# Projekt_Sch.net
KiCad netlist of a schematic drawn in Altium Designer
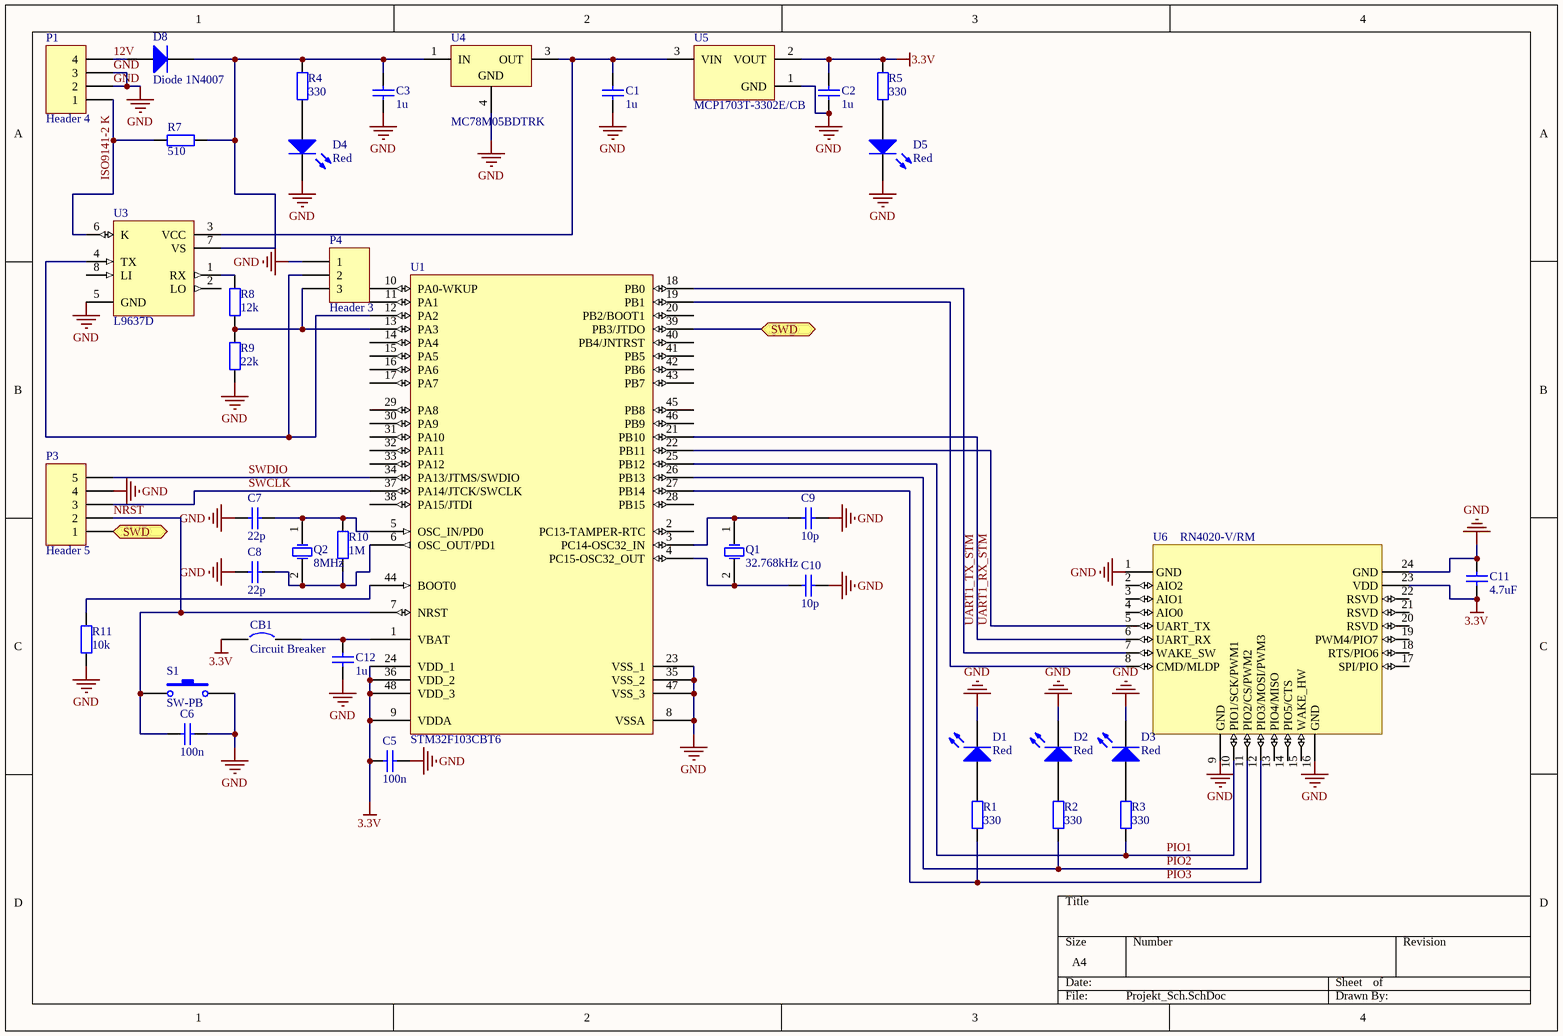
[diagram p0: Projekt_Sch.SchDoc]

(export (version "E")
  (design (tool "Eeschema 10.0.6"))
  (components
    (comp (ref "C1")
      (value "1u")
      (footprint "0402")
      (description "Capacitor")
      (fields (field (name "PUBLISHER") "Altium Limited"))
      (libsource (lib "Miscellaneous Devices") (part "Cap"))
    )
    (comp (ref "C2")
      (value "1u")
      (footprint "0402")
      (description "Capacitor")
      (fields (field (name "PUBLISHER") "Altium Limited"))
      (libsource (lib "Miscellaneous Devices") (part "Cap"))
    )
    (comp (ref "C3")
      (value "1u")
      (footprint "0603")
      (description "Capacitor")
      (fields (field (name "PUBLISHER") "Altium Limited"))
      (libsource (lib "Miscellaneous Devices") (part "Cap"))
    )
    (comp (ref "C5")
      (value "100n")
      (footprint "0402")
      (description "Capacitor")
      (fields (field (name "PUBLISHER") "Altium Limited"))
      (libsource (lib "Miscellaneous Devices") (part "Cap"))
    )
    (comp (ref "C6")
      (value "100n")
      (footprint "0402")
      (description "Capacitor")
      (fields (field (name "PUBLISHER") "Altium Limited"))
      (libsource (lib "Miscellaneous Devices") (part "Cap"))
    )
    (comp (ref "C7")
      (value "22p")
      (footprint "0402")
      (description "Capacitor")
      (fields (field (name "PUBLISHER") "Altium Limited"))
      (libsource (lib "Miscellaneous Devices") (part "Cap"))
    )
    (comp (ref "C8")
      (value "22p")
      (footprint "0402")
      (description "Capacitor")
      (fields (field (name "PUBLISHER") "Altium Limited"))
      (libsource (lib "Miscellaneous Devices") (part "Cap"))
    )
    (comp (ref "C9")
      (value "10p")
      (footprint "0402")
      (description "Capacitor")
      (fields (field (name "PUBLISHER") "Altium Limited"))
      (libsource (lib "Miscellaneous Devices") (part "Cap"))
    )
    (comp (ref "C10")
      (value "10p")
      (footprint "0402")
      (description "Capacitor")
      (fields (field (name "PUBLISHER") "Altium Limited"))
      (libsource (lib "Miscellaneous Devices") (part "Cap"))
    )
    (comp (ref "C11")
      (value "4.7uF")
      (footprint "0402")
      (description "Capacitor")
      (fields (field (name "PUBLISHER") "Altium Limited"))
      (libsource (lib "Miscellaneous Devices") (part "Cap"))
    )
    (comp (ref "C12")
      (value "1u")
      (footprint "0402")
      (description "Capacitor")
      (fields (field (name "PUBLISHER") "Altium Limited"))
      (libsource (lib "Miscellaneous Devices") (part "Cap"))
    )
    (comp (ref "CB1")
      (value "Circuit Breaker")
      (footprint "SPST-2")
      (fields (field (name "PUBLISHER") "Altium Limited"))
      (libsource (lib "Miscellaneous Devices") (part "Circuit Breaker"))
    )
    (comp (ref "D1")
      (value "Red")
      (footprint "0402")
      (description "Typical RED, GREEN, YELLOW, AMBER GaAs LED")
      (fields (field (name "PUBLISHER") "Altium Limited"))
      (libsource (lib "Miscellaneous Devices2") (part "LED2"))
    )
    (comp (ref "D2")
      (value "Red")
      (footprint "0402")
      (description "Typical RED, GREEN, YELLOW, AMBER GaAs LED")
      (fields (field (name "PUBLISHER") "Altium Limited"))
      (libsource (lib "Miscellaneous Devices2") (part "LED2"))
    )
    (comp (ref "D3")
      (value "Red")
      (footprint "0402")
      (description "Typical RED, GREEN, YELLOW, AMBER GaAs LED")
      (fields (field (name "PUBLISHER") "Altium Limited"))
      (libsource (lib "Miscellaneous Devices2") (part "LED2"))
    )
    (comp (ref "D4")
      (value "Red")
      (footprint "0402")
      (description "Typical RED, GREEN, YELLOW, AMBER GaAs LED")
      (fields (field (name "PUBLISHER") "Altium Limited"))
      (libsource (lib "Miscellaneous Devices2") (part "LED2"))
    )
    (comp (ref "D5")
      (value "Red")
      (footprint "0402")
      (description "Typical RED, GREEN, YELLOW, AMBER GaAs LED")
      (fields (field (name "PUBLISHER") "Altium Limited"))
      (libsource (lib "Miscellaneous Devices2") (part "LED2"))
    )
    (comp (ref "D8")
      (value "Diode 1N4007")
      (footprint "DO-41")
      (description "1 Amp General Purpose Rectifier")
      (fields (field (name "PUBLISHER") "Altium Limited"))
      (libsource (lib "Miscellaneous Devices") (part "Diode 1N4007"))
    )
    (comp (ref "P1")
      (value "Header 4")
      (footprint "HDR1X4")
      (description "Header, 4-Pin")
      (fields (field (name "PUBLISHER") "Altium Limited"))
      (libsource (lib "Miscellaneous Connectors") (part "Header 4"))
    )
    (comp (ref "P3")
      (value "Header 5")
      (footprint "HDR1X5")
      (description "Header, 5-Pin")
      (fields (field (name "PUBLISHER") "Altium Limited"))
      (libsource (lib "Miscellaneous Connectors") (part "Header 5"))
    )
    (comp (ref "P4")
      (value "Header 3")
      (footprint "HDR1X3")
      (description "Header, 3-Pin")
      (fields (field (name "PUBLISHER") "Altium Limited"))
      (libsource (lib "Miscellaneous Connectors") (part "Header 3"))
    )
    (comp (ref "Q1")
      (value "32.768kHz")
      (footprint "Kwarc")
      (description "Crystal Oscillator")
      (fields (field (name "PUBLISHER") "Altium Limited"))
      (libsource (lib "Miscellaneous Devices2") (part "XTAL"))
    )
    (comp (ref "Q2")
      (value "8MHz")
      (footprint "HC-49U")
      (description "Crystal Oscillator")
      (fields (field (name "PUBLISHER") "Altium Limited"))
      (libsource (lib "ECS Crystal Oscillator") (part "ECS-10-13-1"))
    )
    (comp (ref "R1")
      (value "330")
      (footprint "0402")
      (description "Resistor")
      (fields (field (name "PUBLISHER") "Altium Limited"))
      (libsource (lib "") (part "Res2_2"))
    )
    (comp (ref "R2")
      (value "330")
      (footprint "0402")
      (description "Resistor")
      (fields (field (name "PUBLISHER") "Altium Limited"))
      (libsource (lib "") (part "Res2_2"))
    )
    (comp (ref "R3")
      (value "330")
      (footprint "0402")
      (description "Resistor")
      (fields (field (name "PUBLISHER") "Altium Limited"))
      (libsource (lib "") (part "Res2_2"))
    )
    (comp (ref "R4")
      (value "330")
      (footprint "0402")
      (description "Resistor")
      (fields (field (name "PUBLISHER") "Altium Limited"))
      (libsource (lib "Miscellaneous Devices") (part "Res2"))
    )
    (comp (ref "R5")
      (value "330")
      (footprint "0402")
      (description "Resistor")
      (fields (field (name "PUBLISHER") "Altium Limited"))
      (libsource (lib "Miscellaneous Devices") (part "Res2"))
    )
    (comp (ref "R7")
      (value "510")
      (footprint "0402")
      (description "Resistor")
      (fields (field (name "PUBLISHER") "Altium Limited"))
      (libsource (lib "") (part "Res2_1"))
    )
    (comp (ref "R8")
      (value "12k")
      (footprint "0402")
      (description "Resistor")
      (fields (field (name "PUBLISHER") "Altium Limited"))
      (libsource (lib "Miscellaneous Devices") (part "Res2"))
    )
    (comp (ref "R9")
      (value "22k")
      (footprint "0402")
      (description "Resistor")
      (fields (field (name "PUBLISHER") "Altium Limited"))
      (libsource (lib "Miscellaneous Devices") (part "Res2"))
    )
    (comp (ref "R10")
      (value "1M")
      (footprint "0402")
      (description "Resistor")
      (fields (field (name "PUBLISHER") "Altium Limited"))
      (libsource (lib "Miscellaneous Devices") (part "Res2"))
    )
    (comp (ref "R11")
      (value "10k")
      (footprint "0402")
      (description "Resistor")
      (fields (field (name "PUBLISHER") "Altium Limited"))
      (libsource (lib "") (part "Res2_2"))
    )
    (comp (ref "S1")
      (value "SW-PB")
      (footprint "SPST-2")
      (description "Switch")
      (fields (field (name "PUBLISHER") "Altium Limited"))
      (libsource (lib "Miscellaneous Devices") (part "SW-PB"))
    )
    (comp (ref "U1")
      (value "STM32F103CBT6")
      (footprint "LQFP48_N")
      (description "STM32 ARM-based 32-bit MCU with 128 Kbytes Flash, 48-pin LQFP, Industrial Temperature")
      (fields (field (name "PUBLISHER") "Altium Limited"))
      (libsource (lib "ST Microcontroller 32-Bit STM32") (part "STM32F103CBT6"))
    )
    (comp (ref "U3")
      (value "L9637D")
      (footprint "SO8_N")
      (description "ISO 9141 Interface")
      (fields (field (name "PUBLISHER") "Altium Limited"))
      (libsource (lib "ST Automotive Diagnostic Serial Link") (part "L9637D"))
    )
    (comp (ref "U4")
      (value "MC78M05BDTRK")
      (footprint "369A-13")
      (description "Three-Terminal Medium Current Positive Voltage Regulator")
      (fields (field (name "PUBLISHER") "Altium Limited"))
      (libsource (lib "ON Semi Power Mgt Voltage Regulator") (part "MC78M05BDTRK"))
    )
    (comp (ref "U5")
      (value "MCP1703T-3302E/CB")
      (footprint "SOT-23A-CB3_N")
      (fields (field (name "PUBLISHER") "Altium Limited"))
      (libsource (lib "Microchip Power Mgt Line Regulator") (part "MCP1703T-3302E/CB"))
    )
    (comp (ref "U6")
      (value "RN4020-V/RM")
      (footprint "RN4020_ALT")
      (description "Microchip RN4020 Bluetooth")
      (libsource (lib "MicrochipTechnology") (part "RN2020-V/RM123"))
    )
  )
  (nets
    (net (code "1") (name "/12V") (class "Default")
      (node (ref "D8") (pin "1") (pinfunction "A_1") (pintype "passive"))
      (node (ref "P1") (pin "4") (pinfunction "4_4") (pintype "passive"))
    )
    (net (code "2") (name "/ISO9141-2 K") (class "Default")
      (node (ref "P1") (pin "1") (pinfunction "1_1") (pintype "passive"))
      (node (ref "R7") (pin "2") (pinfunction "2_2") (pintype "passive"))
      (node (ref "U3") (pin "6") (pinfunction "K_6") (pintype "bidirectional"))
    )
    (net (code "3") (name "/NRST") (class "Default")
      (node (ref "C6") (pin "2") (pinfunction "2_2") (pintype "passive"))
      (node (ref "P3") (pin "2") (pinfunction "2_2") (pintype "passive"))
      (node (ref "S1") (pin "1") (pinfunction "1_1") (pintype "passive"))
      (node (ref "U1") (pin "7") (pinfunction "NRST_7") (pintype "bidirectional"))
    )
    (net (code "4") (name "/PIO1") (class "Default")
      (node (ref "R3") (pin "2") (pinfunction "2_2") (pintype "passive"))
      (node (ref "U1") (pin "25") (pinfunction "PB12_25") (pintype "bidirectional"))
      (node (ref "U6") (pin "10") (pinfunction "PIO1/SCK/PWM1_10") (pintype "bidirectional"))
    )
    (net (code "5") (name "/PIO2") (class "Default")
      (node (ref "R2") (pin "2") (pinfunction "2_2") (pintype "passive"))
      (node (ref "U1") (pin "26") (pinfunction "PB13_26") (pintype "bidirectional"))
      (node (ref "U6") (pin "11") (pinfunction "PIO2/CS/PWM2_11") (pintype "bidirectional"))
    )
    (net (code "6") (name "/PIO3") (class "Default")
      (node (ref "R1") (pin "2") (pinfunction "2_2") (pintype "passive"))
      (node (ref "U1") (pin "27") (pinfunction "PB14_27") (pintype "bidirectional"))
      (node (ref "U6") (pin "12") (pinfunction "PIO3/MOSI/PWM3_12") (pintype "bidirectional"))
    )
    (net (code "7") (name "/SWCLK") (class "Default")
      (node (ref "P3") (pin "3") (pinfunction "3_3") (pintype "passive"))
      (node (ref "U1") (pin "37") (pinfunction "PA14/JTCK/SWCLK_37") (pintype "bidirectional"))
    )
    (net (code "8") (name "/SWD") (class "Default")
      (node (ref "P3") (pin "1") (pinfunction "1_1") (pintype "passive"))
      (node (ref "U1") (pin "39") (pinfunction "PB3/JTDO_39") (pintype "bidirectional"))
    )
    (net (code "9") (name "/SWDIO") (class "Default")
      (node (ref "P3") (pin "5") (pinfunction "5_5") (pintype "passive"))
      (node (ref "U1") (pin "34") (pinfunction "PA13/JTMS/SWDIO_34") (pintype "bidirectional"))
    )
    (net (code "10") (name "/UART1_RX_STM") (class "Default")
      (node (ref "U1") (pin "22") (pinfunction "PB11_22") (pintype "bidirectional"))
      (node (ref "U6") (pin "5") (pinfunction "UART_TX_5") (pintype "bidirectional"))
    )
    (net (code "11") (name "/UART1_TX_STM") (class "Default")
      (node (ref "U1") (pin "21") (pinfunction "PB10_21") (pintype "bidirectional"))
      (node (ref "U6") (pin "6") (pinfunction "UART_RX_6") (pintype "bidirectional"))
    )
    (net (code "12") (name "3.3V") (class "Default")
      (node (ref "C11") (pin "1") (pinfunction "1_1") (pintype "passive"))
      (node (ref "C2") (pin "2") (pinfunction "2_2") (pintype "passive"))
      (node (ref "C5") (pin "2") (pinfunction "2_2") (pintype "passive"))
      (node (ref "CB1") (pin "1") (pinfunction "1_1") (pintype "passive"))
      (node (ref "R5") (pin "2") (pinfunction "2_2") (pintype "passive"))
      (node (ref "U1") (pin "24") (pinfunction "VDD_1_24") (pintype "power_in"))
      (node (ref "U1") (pin "36") (pinfunction "VDD_2_36") (pintype "power_in"))
      (node (ref "U1") (pin "48") (pinfunction "VDD_3_48") (pintype "power_in"))
      (node (ref "U1") (pin "9") (pinfunction "VDDA_9") (pintype "power_in"))
      (node (ref "U5") (pin "2") (pinfunction "VOUT_2") (pintype "power_in"))
      (node (ref "U6") (pin "23") (pinfunction "VDD_23") (pintype "power_in"))
    )
    (net (code "13") (name "GND") (class "Default")
      (node (ref "C1") (pin "1") (pinfunction "1_1") (pintype "passive"))
      (node (ref "C10") (pin "1") (pinfunction "1_1") (pintype "passive"))
      (node (ref "C11") (pin "2") (pinfunction "2_2") (pintype "passive"))
      (node (ref "C12") (pin "1") (pinfunction "1_1") (pintype "passive"))
      (node (ref "C2") (pin "1") (pinfunction "1_1") (pintype "passive"))
      (node (ref "C3") (pin "1") (pinfunction "1_1") (pintype "passive"))
      (node (ref "C5") (pin "1") (pinfunction "1_1") (pintype "passive"))
      (node (ref "C6") (pin "1") (pinfunction "1_1") (pintype "passive"))
      (node (ref "C7") (pin "2") (pinfunction "2_2") (pintype "passive"))
      (node (ref "C8") (pin "2") (pinfunction "2_2") (pintype "passive"))
      (node (ref "C9") (pin "1") (pinfunction "1_1") (pintype "passive"))
      (node (ref "D1") (pin "2") (pinfunction "K_2") (pintype "passive"))
      (node (ref "D2") (pin "2") (pinfunction "K_2") (pintype "passive"))
      (node (ref "D3") (pin "2") (pinfunction "K_2") (pintype "passive"))
      (node (ref "D4") (pin "2") (pinfunction "K_2") (pintype "passive"))
      (node (ref "D5") (pin "2") (pinfunction "K_2") (pintype "passive"))
      (node (ref "P1") (pin "2") (pinfunction "2_2") (pintype "passive"))
      (node (ref "P1") (pin "3") (pinfunction "3_3") (pintype "passive"))
      (node (ref "P3") (pin "4") (pinfunction "4_4") (pintype "passive"))
      (node (ref "P4") (pin "1") (pinfunction "1_1") (pintype "passive"))
      (node (ref "R11") (pin "2") (pinfunction "2_2") (pintype "passive"))
      (node (ref "R9") (pin "1") (pinfunction "1_1") (pintype "passive"))
      (node (ref "S1") (pin "2") (pinfunction "2_2") (pintype "passive"))
      (node (ref "U1") (pin "23") (pinfunction "VSS_1_23") (pintype "power_in"))
      (node (ref "U1") (pin "35") (pinfunction "VSS_2_35") (pintype "power_in"))
      (node (ref "U1") (pin "47") (pinfunction "VSS_3_47") (pintype "power_in"))
      (node (ref "U1") (pin "8") (pinfunction "VSSA_8") (pintype "power_in"))
      (node (ref "U3") (pin "5") (pinfunction "GND_5") (pintype "power_in"))
      (node (ref "U4") (pin "4") (pinfunction "GND_4") (pintype "power_in"))
      (node (ref "U5") (pin "1") (pinfunction "GND_1") (pintype "power_in"))
      (node (ref "U6") (pin "1") (pinfunction "GND_1") (pintype "power_in"))
      (node (ref "U6") (pin "16") (pinfunction "GND_16") (pintype "power_in"))
      (node (ref "U6") (pin "24") (pinfunction "GND_24") (pintype "power_in"))
      (node (ref "U6") (pin "9") (pinfunction "GND_9") (pintype "power_in"))
    )
    (net (code "14") (name "Net-(D1-A)") (class "Default")
      (node (ref "D1") (pin "1") (pinfunction "A_1") (pintype "passive"))
      (node (ref "R1") (pin "1") (pinfunction "1_1") (pintype "passive"))
    )
    (net (code "15") (name "Net-(D2-A)") (class "Default")
      (node (ref "D2") (pin "1") (pinfunction "A_1") (pintype "passive"))
      (node (ref "R2") (pin "1") (pinfunction "1_1") (pintype "passive"))
    )
    (net (code "16") (name "Net-(D3-A)") (class "Default")
      (node (ref "D3") (pin "1") (pinfunction "A_1") (pintype "passive"))
      (node (ref "R3") (pin "1") (pinfunction "1_1") (pintype "passive"))
    )
    (net (code "17") (name "Net-(D4-A)") (class "Default")
      (node (ref "D4") (pin "1") (pinfunction "A_1") (pintype "passive"))
      (node (ref "R4") (pin "1") (pinfunction "1_1") (pintype "passive"))
    )
    (net (code "18") (name "Net-(D5-A)") (class "Default")
      (node (ref "D5") (pin "1") (pinfunction "A_1") (pintype "passive"))
      (node (ref "R5") (pin "1") (pinfunction "1_1") (pintype "passive"))
    )
    (net (code "19") (name "Net-(D8-K)") (class "Default")
      (node (ref "C3") (pin "2") (pinfunction "2_2") (pintype "passive"))
      (node (ref "D8") (pin "2") (pinfunction "K_2") (pintype "passive"))
      (node (ref "R4") (pin "2") (pinfunction "2_2") (pintype "passive"))
      (node (ref "R7") (pin "1") (pinfunction "1_1") (pintype "passive"))
      (node (ref "U3") (pin "7") (pinfunction "VS_7") (pintype "power_in"))
      (node (ref "U4") (pin "1") (pinfunction "IN_1") (pintype "power_in"))
    )
    (net (code "20") (name "Net-(Q1-OSC1)") (class "Default")
      (node (ref "C9") (pin "2") (pinfunction "2_2") (pintype "passive"))
      (node (ref "Q1") (pin "1") (pinfunction "OSC1_1") (pintype "passive"))
      (node (ref "U1") (pin "3") (pinfunction "PC14-OSC32_IN_3") (pintype "bidirectional"))
    )
    (net (code "21") (name "Net-(Q1-OSC2)") (class "Default")
      (node (ref "C10") (pin "2") (pinfunction "2_2") (pintype "passive"))
      (node (ref "Q1") (pin "2") (pinfunction "OSC2_2") (pintype "passive"))
      (node (ref "U1") (pin "4") (pinfunction "PC15-OSC32_OUT_4") (pintype "bidirectional"))
    )
    (net (code "22") (name "Net-(Q2-OSC1)") (class "Default")
      (node (ref "C7") (pin "1") (pinfunction "1_1") (pintype "passive"))
      (node (ref "Q2") (pin "1") (pinfunction "OSC1_1") (pintype "passive"))
      (node (ref "R10") (pin "2") (pinfunction "2_2") (pintype "passive"))
      (node (ref "U1") (pin "5") (pinfunction "OSC_IN/PD0_5") (pintype "input"))
    )
    (net (code "23") (name "Net-(Q2-OSC2)") (class "Default")
      (node (ref "C8") (pin "1") (pinfunction "1_1") (pintype "passive"))
      (node (ref "Q2") (pin "2") (pinfunction "OSC2_2") (pintype "passive"))
      (node (ref "R10") (pin "1") (pinfunction "1_1") (pintype "passive"))
      (node (ref "U1") (pin "6") (pinfunction "OSC_OUT/PD1_6") (pintype "output"))
    )
    (net (code "24") (name "Net-(U1-BOOT0)") (class "Default")
      (node (ref "R11") (pin "1") (pinfunction "1_1") (pintype "passive"))
      (node (ref "U1") (pin "44") (pinfunction "BOOT0_44") (pintype "input"))
    )
    (net (code "25") (name "Net-(U1-PA2)") (class "Default")
      (node (ref "P4") (pin "2") (pinfunction "2_2") (pintype "passive"))
      (node (ref "U1") (pin "12") (pinfunction "PA2_12") (pintype "bidirectional"))
      (node (ref "U3") (pin "4") (pinfunction "TX_4") (pintype "input"))
    )
    (net (code "26") (name "Net-(U1-PA3)") (class "Default")
      (node (ref "P4") (pin "3") (pinfunction "3_3") (pintype "passive"))
      (node (ref "R8") (pin "1") (pinfunction "1_1") (pintype "passive"))
      (node (ref "R9") (pin "2") (pinfunction "2_2") (pintype "passive"))
      (node (ref "U1") (pin "13") (pinfunction "PA3_13") (pintype "bidirectional"))
    )
    (net (code "27") (name "Net-(U1-PB0)") (class "Default")
      (node (ref "U1") (pin "18") (pinfunction "PB0_18") (pintype "bidirectional"))
      (node (ref "U6") (pin "7") (pinfunction "WAKE_SW_7") (pintype "bidirectional"))
    )
    (net (code "28") (name "Net-(U1-PB1)") (class "Default")
      (node (ref "U1") (pin "19") (pinfunction "PB1_19") (pintype "bidirectional"))
      (node (ref "U6") (pin "8") (pinfunction "CMD/MLDP_8") (pintype "bidirectional"))
    )
    (net (code "29") (name "Net-(U1-VBAT)") (class "Default")
      (node (ref "C12") (pin "2") (pinfunction "2_2") (pintype "passive"))
      (node (ref "CB1") (pin "2") (pinfunction "2_2") (pintype "passive"))
      (node (ref "U1") (pin "1") (pinfunction "VBAT_1") (pintype "power_in"))
    )
    (net (code "30") (name "Net-(U3-RX)") (class "Default")
      (node (ref "R8") (pin "2") (pinfunction "2_2") (pintype "passive"))
      (node (ref "U3") (pin "1") (pinfunction "RX_1") (pintype "output"))
    )
    (net (code "31") (name "Net-(U3-VCC)") (class "Default")
      (node (ref "C1") (pin "2") (pinfunction "2_2") (pintype "passive"))
      (node (ref "U3") (pin "3") (pinfunction "VCC_3") (pintype "power_in"))
      (node (ref "U4") (pin "3") (pinfunction "OUT_3") (pintype "power_in"))
      (node (ref "U5") (pin "3") (pinfunction "VIN_3") (pintype "power_in"))
    )
    (net (code "32") (name "unconnected-(U1-PA0-WKUP-Pad10)") (class "Default")
      (node (ref "U1") (pin "10") (pinfunction "PA0-WKUP_10") (pintype "bidirectional"))
    )
    (net (code "33") (name "unconnected-(U1-PA1-Pad11)") (class "Default")
      (node (ref "U1") (pin "11") (pinfunction "PA1_11") (pintype "bidirectional"))
    )
    (net (code "34") (name "unconnected-(U1-PA4-Pad14)") (class "Default")
      (node (ref "U1") (pin "14") (pinfunction "PA4_14") (pintype "bidirectional"))
    )
    (net (code "35") (name "unconnected-(U1-PA5-Pad15)") (class "Default")
      (node (ref "U1") (pin "15") (pinfunction "PA5_15") (pintype "bidirectional"))
    )
    (net (code "36") (name "unconnected-(U1-PA6-Pad16)") (class "Default")
      (node (ref "U1") (pin "16") (pinfunction "PA6_16") (pintype "bidirectional"))
    )
    (net (code "37") (name "unconnected-(U1-PA7-Pad17)") (class "Default")
      (node (ref "U1") (pin "17") (pinfunction "PA7_17") (pintype "bidirectional"))
    )
    (net (code "38") (name "unconnected-(U1-PA8-Pad29)") (class "Default")
      (node (ref "U1") (pin "29") (pinfunction "PA8_29") (pintype "bidirectional"))
    )
    (net (code "39") (name "unconnected-(U1-PA9-Pad30)") (class "Default")
      (node (ref "U1") (pin "30") (pinfunction "PA9_30") (pintype "bidirectional"))
    )
    (net (code "40") (name "unconnected-(U1-PA10-Pad31)") (class "Default")
      (node (ref "U1") (pin "31") (pinfunction "PA10_31") (pintype "bidirectional"))
    )
    (net (code "41") (name "unconnected-(U1-PA11-Pad32)") (class "Default")
      (node (ref "U1") (pin "32") (pinfunction "PA11_32") (pintype "bidirectional"))
    )
    (net (code "42") (name "unconnected-(U1-PA12-Pad33)") (class "Default")
      (node (ref "U1") (pin "33") (pinfunction "PA12_33") (pintype "bidirectional"))
    )
    (net (code "43") (name "unconnected-(U1-PA15{slash}JTDI-Pad38)") (class "Default")
      (node (ref "U1") (pin "38") (pinfunction "PA15/JTDI_38") (pintype "bidirectional"))
    )
    (net (code "44") (name "unconnected-(U1-PB2{slash}BOOT1-Pad20)") (class "Default")
      (node (ref "U1") (pin "20") (pinfunction "PB2/BOOT1_20") (pintype "bidirectional"))
    )
    (net (code "45") (name "unconnected-(U1-PB4{slash}JNTRST-Pad40)") (class "Default")
      (node (ref "U1") (pin "40") (pinfunction "PB4/JNTRST_40") (pintype "bidirectional"))
    )
    (net (code "46") (name "unconnected-(U1-PB5-Pad41)") (class "Default")
      (node (ref "U1") (pin "41") (pinfunction "PB5_41") (pintype "bidirectional"))
    )
    (net (code "47") (name "unconnected-(U1-PB6-Pad42)") (class "Default")
      (node (ref "U1") (pin "42") (pinfunction "PB6_42") (pintype "bidirectional"))
    )
    (net (code "48") (name "unconnected-(U1-PB7-Pad43)") (class "Default")
      (node (ref "U1") (pin "43") (pinfunction "PB7_43") (pintype "bidirectional"))
    )
    (net (code "49") (name "unconnected-(U1-PB8-Pad45)") (class "Default")
      (node (ref "U1") (pin "45") (pinfunction "PB8_45") (pintype "bidirectional"))
    )
    (net (code "50") (name "unconnected-(U1-PB9-Pad46)") (class "Default")
      (node (ref "U1") (pin "46") (pinfunction "PB9_46") (pintype "bidirectional"))
    )
    (net (code "51") (name "unconnected-(U1-PB15-Pad28)") (class "Default")
      (node (ref "U1") (pin "28") (pinfunction "PB15_28") (pintype "bidirectional"))
    )
    (net (code "52") (name "unconnected-(U1-PC13-TAMPER-RTC-Pad2)") (class "Default")
      (node (ref "U1") (pin "2") (pinfunction "PC13-TAMPER-RTC_2") (pintype "bidirectional"))
    )
    (net (code "53") (name "unconnected-(U3-LI-Pad8)") (class "Default")
      (node (ref "U3") (pin "8") (pinfunction "LI_8") (pintype "input"))
    )
    (net (code "54") (name "unconnected-(U3-LO-Pad2)") (class "Default")
      (node (ref "U3") (pin "2") (pinfunction "LO_2") (pintype "output"))
    )
    (net (code "55") (name "unconnected-(U6-AIO0-Pad4)") (class "Default")
      (node (ref "U6") (pin "4") (pinfunction "AIO0_4") (pintype "bidirectional"))
    )
    (net (code "56") (name "unconnected-(U6-AIO1-Pad3)") (class "Default")
      (node (ref "U6") (pin "3") (pinfunction "AIO1_3") (pintype "bidirectional"))
    )
    (net (code "57") (name "unconnected-(U6-AIO2-Pad2)") (class "Default")
      (node (ref "U6") (pin "2") (pinfunction "AIO2_2") (pintype "bidirectional"))
    )
    (net (code "58") (name "unconnected-(U6-PIO4{slash}MISO-Pad13)") (class "Default")
      (node (ref "U6") (pin "13") (pinfunction "PIO4/MISO_13") (pintype "bidirectional"))
    )
    (net (code "59") (name "unconnected-(U6-PIO5{slash}CTS-Pad14)") (class "Default")
      (node (ref "U6") (pin "14") (pinfunction "PIO5/CTS_14") (pintype "bidirectional"))
    )
    (net (code "60") (name "unconnected-(U6-PWM4{slash}PIO7-Pad19)") (class "Default")
      (node (ref "U6") (pin "19") (pinfunction "PWM4/PIO7_19") (pintype "bidirectional"))
    )
    (net (code "61") (name "unconnected-(U6-RSVD-Pad20)") (class "Default")
      (node (ref "U6") (pin "20") (pinfunction "RSVD_20") (pintype "bidirectional"))
    )
    (net (code "62") (name "unconnected-(U6-RSVD-Pad21)") (class "Default")
      (node (ref "U6") (pin "21") (pinfunction "RSVD_21") (pintype "bidirectional"))
    )
    (net (code "63") (name "unconnected-(U6-RSVD-Pad22)") (class "Default")
      (node (ref "U6") (pin "22") (pinfunction "RSVD_22") (pintype "bidirectional"))
    )
    (net (code "64") (name "unconnected-(U6-RTS{slash}PIO6-Pad18)") (class "Default")
      (node (ref "U6") (pin "18") (pinfunction "RTS/PIO6_18") (pintype "bidirectional"))
    )
    (net (code "65") (name "unconnected-(U6-SPI{slash}PIO-Pad17)") (class "Default")
      (node (ref "U6") (pin "17") (pinfunction "SPI/PIO_17") (pintype "bidirectional"))
    )
    (net (code "66") (name "unconnected-(U6-WAKE_HW-Pad15)") (class "Default")
      (node (ref "U6") (pin "15") (pinfunction "WAKE_HW_15") (pintype "bidirectional"))
    )
  )
)
